# External_Stepper.net
KiCad netlist of a schematic drawn in Altium Designer
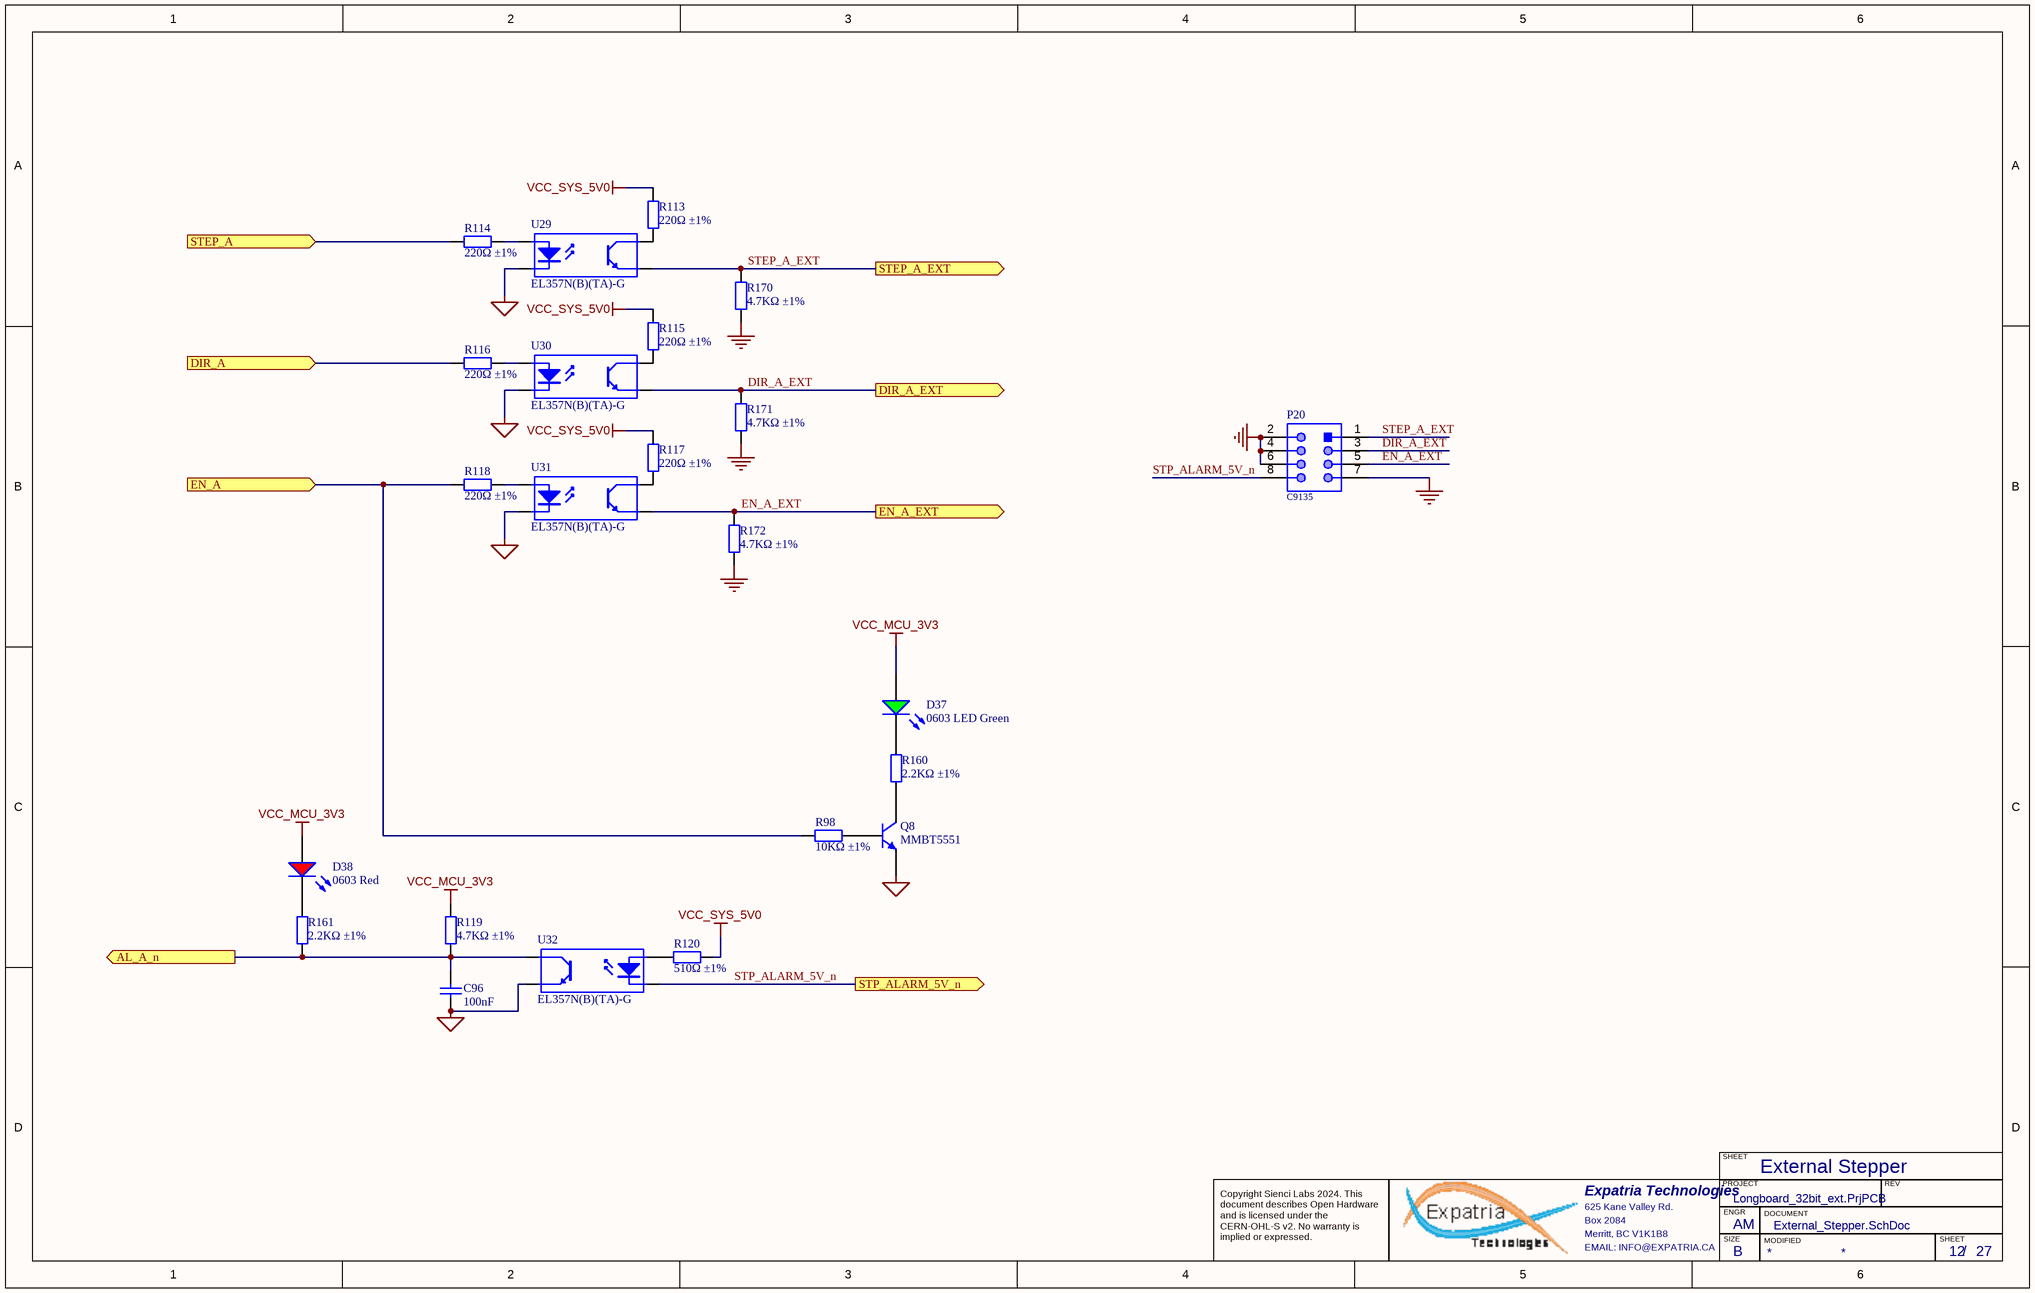
[diagram p0: External_Stepper.SchDoc]

(export (version "E")
  (design (tool "Eeschema 10.0.6"))
  (components
    (comp (ref "C96")
      (value "100nF")
      (footprint "0402_C")
      (description "16V 100nF X7R ±10% 0402 Multilayer Ceramic Capacitors MLCC - SMD/SMT ROHS")
      (fields (field (name "MANUFACTURER") "Samsung Electro-Mechanics") (field (name "TOLERANCE") "10%"))
      (libsource (lib "Sienci_Labs") (part "0402 100nF (104) 10% 16V"))
    )
    (comp (ref "D37")
      (value "0603 LED Green")
      (footprint "0603_LED_S1 - GREEN")
      (description "20mA -40℃~+85℃ 515nm~530nm Emerald 120° 60mW 0603 Light Emitting Diodes (LED) ROHS")
      (fields (field (name "MANUFACTURER PART NUMBER") "MHT192UGCT") (field (name "MANUFACTURER") "MEIHUA"))
      (libsource (lib "Sienci_Labs") (part "MHT192UGCT"))
    )
    (comp (ref "D38")
      (value "0603 Red")
      (footprint "0603_LED_S1")
      (description "-40℃~+85℃ Red 0603 Light Emitting Diodes (LED) ROHS")
      (fields
        (field (name "MANUFACTURER") "Hubei KENTO Elec")
        (field (name "MANUFACTURER PART NUMBER") "KT-0603R")
      )
      (libsource (lib "Sienci_Labs") (part "KT-0603R"))
    )
    (comp (ref "P20")
      (value "C9135")
      (footprint "61200821621")
      (description "Male Box Header WR-BHD, THT, Vertical, pitch 2.54 mm, 8 pins")
      (fields
        (field (name "MANUFACTURER") "Wurth Electronics")
        (field (name "MANUFACTURER PART NUMBER") "61200821621")
        (field (name "PUBLISHER") "WurthElektronik")
      )
      (libsource (lib "Sienci_Labs") (part "HDR2x4P"))
    )
    (comp (ref "Q8")
      (value "MMBT5551")
      (footprint "SOT-23(SOT-23-3)")
      (fields (field (name "MANUFACTURER") "Jiangsu Changjing Electronics Technology"))
      (libsource (lib "Sienci_Labs") (part "MMBT5551"))
    )
    (comp (ref "R98")
      (value "10KΩ ±1%")
      (footprint "0603_R")
      (description "Chip resistor")
      (fields
        (field (name "MANUFACTURER") "Uniroyal Elec")
        (field (name "MANUFACTURER PART NUMBER") "0603WAF1002T5E")
      )
      (libsource (lib "Sienci_Labs") (part "0603 10K (1002) 1%"))
    )
    (comp (ref "R113")
      (value "220Ω ±1%")
      (footprint "0402_R")
      (description "Chip resistor")
      (fields
        (field (name "MANUFACTURER") "Uniroyal Elec")
        (field (name "MANUFACTURER PART NUMBER") "0402WGF2200TCE")
      )
      (libsource (lib "") (part "0402 220R (2200) 1%_1"))
    )
    (comp (ref "R114")
      (value "220Ω ±1%")
      (footprint "0402_R")
      (description "Chip resistor")
      (fields
        (field (name "MANUFACTURER") "Uniroyal Elec")
        (field (name "MANUFACTURER PART NUMBER") "0402WGF2200TCE")
      )
      (libsource (lib "RES") (part "0402 220R (2200) 1%"))
    )
    (comp (ref "R115")
      (value "220Ω ±1%")
      (footprint "0402_R")
      (description "Chip resistor")
      (fields
        (field (name "MANUFACTURER") "Uniroyal Elec")
        (field (name "MANUFACTURER PART NUMBER") "0402WGF2200TCE")
      )
      (libsource (lib "") (part "0402 220R (2200) 1%_1"))
    )
    (comp (ref "R116")
      (value "220Ω ±1%")
      (footprint "0402_R")
      (description "Chip resistor")
      (fields
        (field (name "MANUFACTURER") "Uniroyal Elec")
        (field (name "MANUFACTURER PART NUMBER") "0402WGF2200TCE")
      )
      (libsource (lib "RES") (part "0402 220R (2200) 1%"))
    )
    (comp (ref "R117")
      (value "220Ω ±1%")
      (footprint "0402_R")
      (description "Chip resistor")
      (fields
        (field (name "MANUFACTURER") "Uniroyal Elec")
        (field (name "MANUFACTURER PART NUMBER") "0402WGF2200TCE")
      )
      (libsource (lib "") (part "0402 220R (2200) 1%_1"))
    )
    (comp (ref "R118")
      (value "220Ω ±1%")
      (footprint "0402_R")
      (description "Chip resistor")
      (fields
        (field (name "MANUFACTURER") "Uniroyal Elec")
        (field (name "MANUFACTURER PART NUMBER") "0402WGF2200TCE")
      )
      (libsource (lib "RES") (part "0402 220R (2200) 1%"))
    )
    (comp (ref "R119")
      (value "4.7KΩ ±1%")
      (footprint "0402_R")
      (description "Chip resistor")
      (fields
        (field (name "MANUFACTURER") "Uniroyal Elec")
        (field (name "MANUFACTURER PART NUMBER") "0402WGF4701TCE")
      )
      (libsource (lib "Sienci_Labs") (part "0402 4.7K (4701) 1%"))
    )
    (comp (ref "R120")
      (value "510Ω ±1%")
      (footprint "0402_R")
      (description "Chip resistor")
      (fields
        (field (name "MANUFACTURER") "Uniroyal Elec")
        (field (name "MANUFACTURER PART NUMBER") "0402WGF5100TCE")
      )
      (libsource (lib "RES") (part "0402 510R (5100) 1%"))
    )
    (comp (ref "R160")
      (value "2.2KΩ ±1%")
      (footprint "0402_R")
      (description "Chip resistor")
      (fields
        (field (name "MANUFACTURER") "Uniroyal Elec")
        (field (name "MANUFACTURER PART NUMBER") "0402WGF2201TCE")
      )
      (libsource (lib "RES") (part "0402 2.2K (2201) 1%"))
    )
    (comp (ref "R161")
      (value "2.2KΩ ±1%")
      (footprint "0402_R")
      (description "Chip resistor")
      (fields
        (field (name "MANUFACTURER") "Uniroyal Elec")
        (field (name "MANUFACTURER PART NUMBER") "0402WGF2201TCE")
      )
      (libsource (lib "RES") (part "0402 2.2K (2201) 1%"))
    )
    (comp (ref "R170")
      (value "4.7KΩ ±1%")
      (footprint "0402_R")
      (description "Chip resistor")
      (fields
        (field (name "MANUFACTURER") "Uniroyal Elec")
        (field (name "MANUFACTURER PART NUMBER") "0402WGF4701TCE")
      )
      (libsource (lib "") (part "0402 4.7K (4701) 1%_1"))
    )
    (comp (ref "R171")
      (value "4.7KΩ ±1%")
      (footprint "0402_R")
      (description "Chip resistor")
      (fields
        (field (name "MANUFACTURER") "Uniroyal Elec")
        (field (name "MANUFACTURER PART NUMBER") "0402WGF4701TCE")
      )
      (libsource (lib "") (part "0402 4.7K (4701) 1%_1"))
    )
    (comp (ref "R172")
      (value "4.7KΩ ±1%")
      (footprint "0402_R")
      (description "Chip resistor")
      (fields
        (field (name "MANUFACTURER") "Uniroyal Elec")
        (field (name "MANUFACTURER PART NUMBER") "0402WGF4701TCE")
      )
      (libsource (lib "") (part "0402 4.7K (4701) 1%_1"))
    )
    (comp (ref "U29")
      (value "EL357N(B)(TA)-G")
      (footprint "Miscellaneous Devices LC:SOP-4_P2.54")
      (description "Optocoupler SOP-4, EL357N(B)(TA)-G, Everlight Electronics")
      (fields (field (name "MANUFACTURER") "Everlight"))
      (libsource (lib "Sienci_Labs") (part "EL357N(B)(TA)-G_[C6649]"))
    )
    (comp (ref "U30")
      (value "EL357N(B)(TA)-G")
      (footprint "Miscellaneous Devices LC:SOP-4_P2.54")
      (description "Optocoupler SOP-4, EL357N(B)(TA)-G, Everlight Electronics")
      (fields (field (name "MANUFACTURER") "Everlight"))
      (libsource (lib "Sienci_Labs") (part "EL357N(B)(TA)-G_[C6649]"))
    )
    (comp (ref "U31")
      (value "EL357N(B)(TA)-G")
      (footprint "Miscellaneous Devices LC:SOP-4_P2.54")
      (description "Optocoupler SOP-4, EL357N(B)(TA)-G, Everlight Electronics")
      (fields (field (name "MANUFACTURER") "Everlight"))
      (libsource (lib "Sienci_Labs") (part "EL357N(B)(TA)-G_[C6649]"))
    )
    (comp (ref "U32")
      (value "EL357N(B)(TA)-G")
      (footprint "Miscellaneous Devices LC:SOP-4_P2.54")
      (description "Optocoupler SOP-4, EL357N(B)(TA)-G, Everlight Electronics")
      (fields (field (name "MANUFACTURER") "Everlight"))
      (libsource (lib "Sienci_Labs") (part "EL357N(B)(TA)-G_[C6649]"))
    )
  )
  (nets
    (net (code "1") (name "/AL_A_n") (class "Default")
      (node (ref "C96") (pin "2") (pinfunction "2_2") (pintype "passive"))
      (node (ref "R119") (pin "1") (pinfunction "1_1") (pintype "passive"))
      (node (ref "R161") (pin "1") (pinfunction "1_1") (pintype "passive"))
      (node (ref "U32") (pin "4") (pinfunction "C_4") (pintype "passive"))
    )
    (net (code "2") (name "/DIR_A") (class "Default")
      (node (ref "R116") (pin "1") (pinfunction "1_1") (pintype "passive"))
    )
    (net (code "3") (name "/DIR_A_EXT") (class "Default")
      (node (ref "P20") (pin "3") (pinfunction "3_3") (pintype "passive"))
      (node (ref "R171") (pin "1") (pinfunction "1_1") (pintype "passive"))
      (node (ref "U30") (pin "3") (pinfunction "E_3") (pintype "passive"))
    )
    (net (code "4") (name "/EN_A") (class "Default")
      (node (ref "R118") (pin "1") (pinfunction "1_1") (pintype "passive"))
      (node (ref "R98") (pin "2") (pinfunction "2_2") (pintype "passive"))
    )
    (net (code "5") (name "/EN_A_EXT") (class "Default")
      (node (ref "P20") (pin "5") (pinfunction "5_5") (pintype "passive"))
      (node (ref "R172") (pin "1") (pinfunction "1_1") (pintype "passive"))
      (node (ref "U31") (pin "3") (pinfunction "E_3") (pintype "passive"))
    )
    (net (code "6") (name "/STEP_A") (class "Default")
      (node (ref "R114") (pin "1") (pinfunction "1_1") (pintype "passive"))
    )
    (net (code "7") (name "/STEP_A_EXT") (class "Default")
      (node (ref "P20") (pin "1") (pinfunction "1_1") (pintype "passive"))
      (node (ref "R170") (pin "1") (pinfunction "1_1") (pintype "passive"))
      (node (ref "U29") (pin "3") (pinfunction "E_3") (pintype "passive"))
    )
    (net (code "8") (name "/STP_ALARM_5V_n") (class "Default")
      (node (ref "P20") (pin "8") (pinfunction "8_8") (pintype "passive"))
      (node (ref "U32") (pin "2") (pinfunction "K_2") (pintype "passive"))
    )
    (net (code "9") (name "GND") (class "Default")
      (node (ref "P20") (pin "2") (pinfunction "2_2") (pintype "passive"))
      (node (ref "P20") (pin "4") (pinfunction "4_4") (pintype "passive"))
      (node (ref "P20") (pin "6") (pinfunction "6_6") (pintype "passive"))
      (node (ref "P20") (pin "7") (pinfunction "7_7") (pintype "passive"))
      (node (ref "R170") (pin "2") (pinfunction "2_2") (pintype "passive"))
      (node (ref "R171") (pin "2") (pinfunction "2_2") (pintype "passive"))
      (node (ref "R172") (pin "2") (pinfunction "2_2") (pintype "passive"))
    )
    (net (code "10") (name "MCU_GND") (class "Default")
      (node (ref "C96") (pin "1") (pinfunction "1_1") (pintype "passive"))
      (node (ref "Q8") (pin "2") (pinfunction "E_2") (pintype "passive"))
      (node (ref "U29") (pin "2") (pinfunction "K_2") (pintype "passive"))
      (node (ref "U30") (pin "2") (pinfunction "K_2") (pintype "passive"))
      (node (ref "U31") (pin "2") (pinfunction "K_2") (pintype "passive"))
      (node (ref "U32") (pin "3") (pinfunction "E_3") (pintype "passive"))
    )
    (net (code "11") (name "Net-(D37-PadK)") (class "Default")
      (node (ref "D37") (pin "K") (pinfunction "K_K") (pintype "passive"))
      (node (ref "R160") (pin "2") (pinfunction "2_2") (pintype "passive"))
    )
    (net (code "12") (name "Net-(D38-PadK)") (class "Default")
      (node (ref "D38") (pin "K") (pinfunction "K_K") (pintype "passive"))
      (node (ref "R161") (pin "2") (pinfunction "2_2") (pintype "passive"))
    )
    (net (code "13") (name "Net-(Q8-B)") (class "Default")
      (node (ref "Q8") (pin "1") (pinfunction "B_1") (pintype "passive"))
      (node (ref "R98") (pin "1") (pinfunction "1_1") (pintype "passive"))
    )
    (net (code "14") (name "Net-(Q8-C)") (class "Default")
      (node (ref "Q8") (pin "3") (pinfunction "C_3") (pintype "passive"))
      (node (ref "R160") (pin "1") (pinfunction "1_1") (pintype "passive"))
    )
    (net (code "15") (name "Net-(U29-A)") (class "Default")
      (node (ref "R114") (pin "2") (pinfunction "2_2") (pintype "passive"))
      (node (ref "U29") (pin "1") (pinfunction "A_1") (pintype "passive"))
    )
    (net (code "16") (name "Net-(U29-C)") (class "Default")
      (node (ref "R113") (pin "2") (pinfunction "2_2") (pintype "passive"))
      (node (ref "U29") (pin "4") (pinfunction "C_4") (pintype "passive"))
    )
    (net (code "17") (name "Net-(U30-A)") (class "Default")
      (node (ref "R116") (pin "2") (pinfunction "2_2") (pintype "passive"))
      (node (ref "U30") (pin "1") (pinfunction "A_1") (pintype "passive"))
    )
    (net (code "18") (name "Net-(U30-C)") (class "Default")
      (node (ref "R115") (pin "2") (pinfunction "2_2") (pintype "passive"))
      (node (ref "U30") (pin "4") (pinfunction "C_4") (pintype "passive"))
    )
    (net (code "19") (name "Net-(U31-A)") (class "Default")
      (node (ref "R118") (pin "2") (pinfunction "2_2") (pintype "passive"))
      (node (ref "U31") (pin "1") (pinfunction "A_1") (pintype "passive"))
    )
    (net (code "20") (name "Net-(U31-C)") (class "Default")
      (node (ref "R117") (pin "2") (pinfunction "2_2") (pintype "passive"))
      (node (ref "U31") (pin "4") (pinfunction "C_4") (pintype "passive"))
    )
    (net (code "21") (name "Net-(U32-A)") (class "Default")
      (node (ref "R120") (pin "1") (pinfunction "1_1") (pintype "passive"))
      (node (ref "U32") (pin "1") (pinfunction "A_1") (pintype "passive"))
    )
    (net (code "22") (name "VCC_MCU_3V3") (class "Default")
      (node (ref "D37") (pin "A") (pinfunction "A_A") (pintype "passive"))
      (node (ref "D38") (pin "A") (pinfunction "A_A") (pintype "passive"))
      (node (ref "R119") (pin "2") (pinfunction "2_2") (pintype "passive"))
    )
    (net (code "23") (name "VCC_SYS_5V0") (class "Default")
      (node (ref "R113") (pin "1") (pinfunction "1_1") (pintype "passive"))
      (node (ref "R115") (pin "1") (pinfunction "1_1") (pintype "passive"))
      (node (ref "R117") (pin "1") (pinfunction "1_1") (pintype "passive"))
      (node (ref "R120") (pin "2") (pinfunction "2_2") (pintype "passive"))
    )
  )
)
